# design.net
KiCad netlist of a schematic drawn in Altium Designer
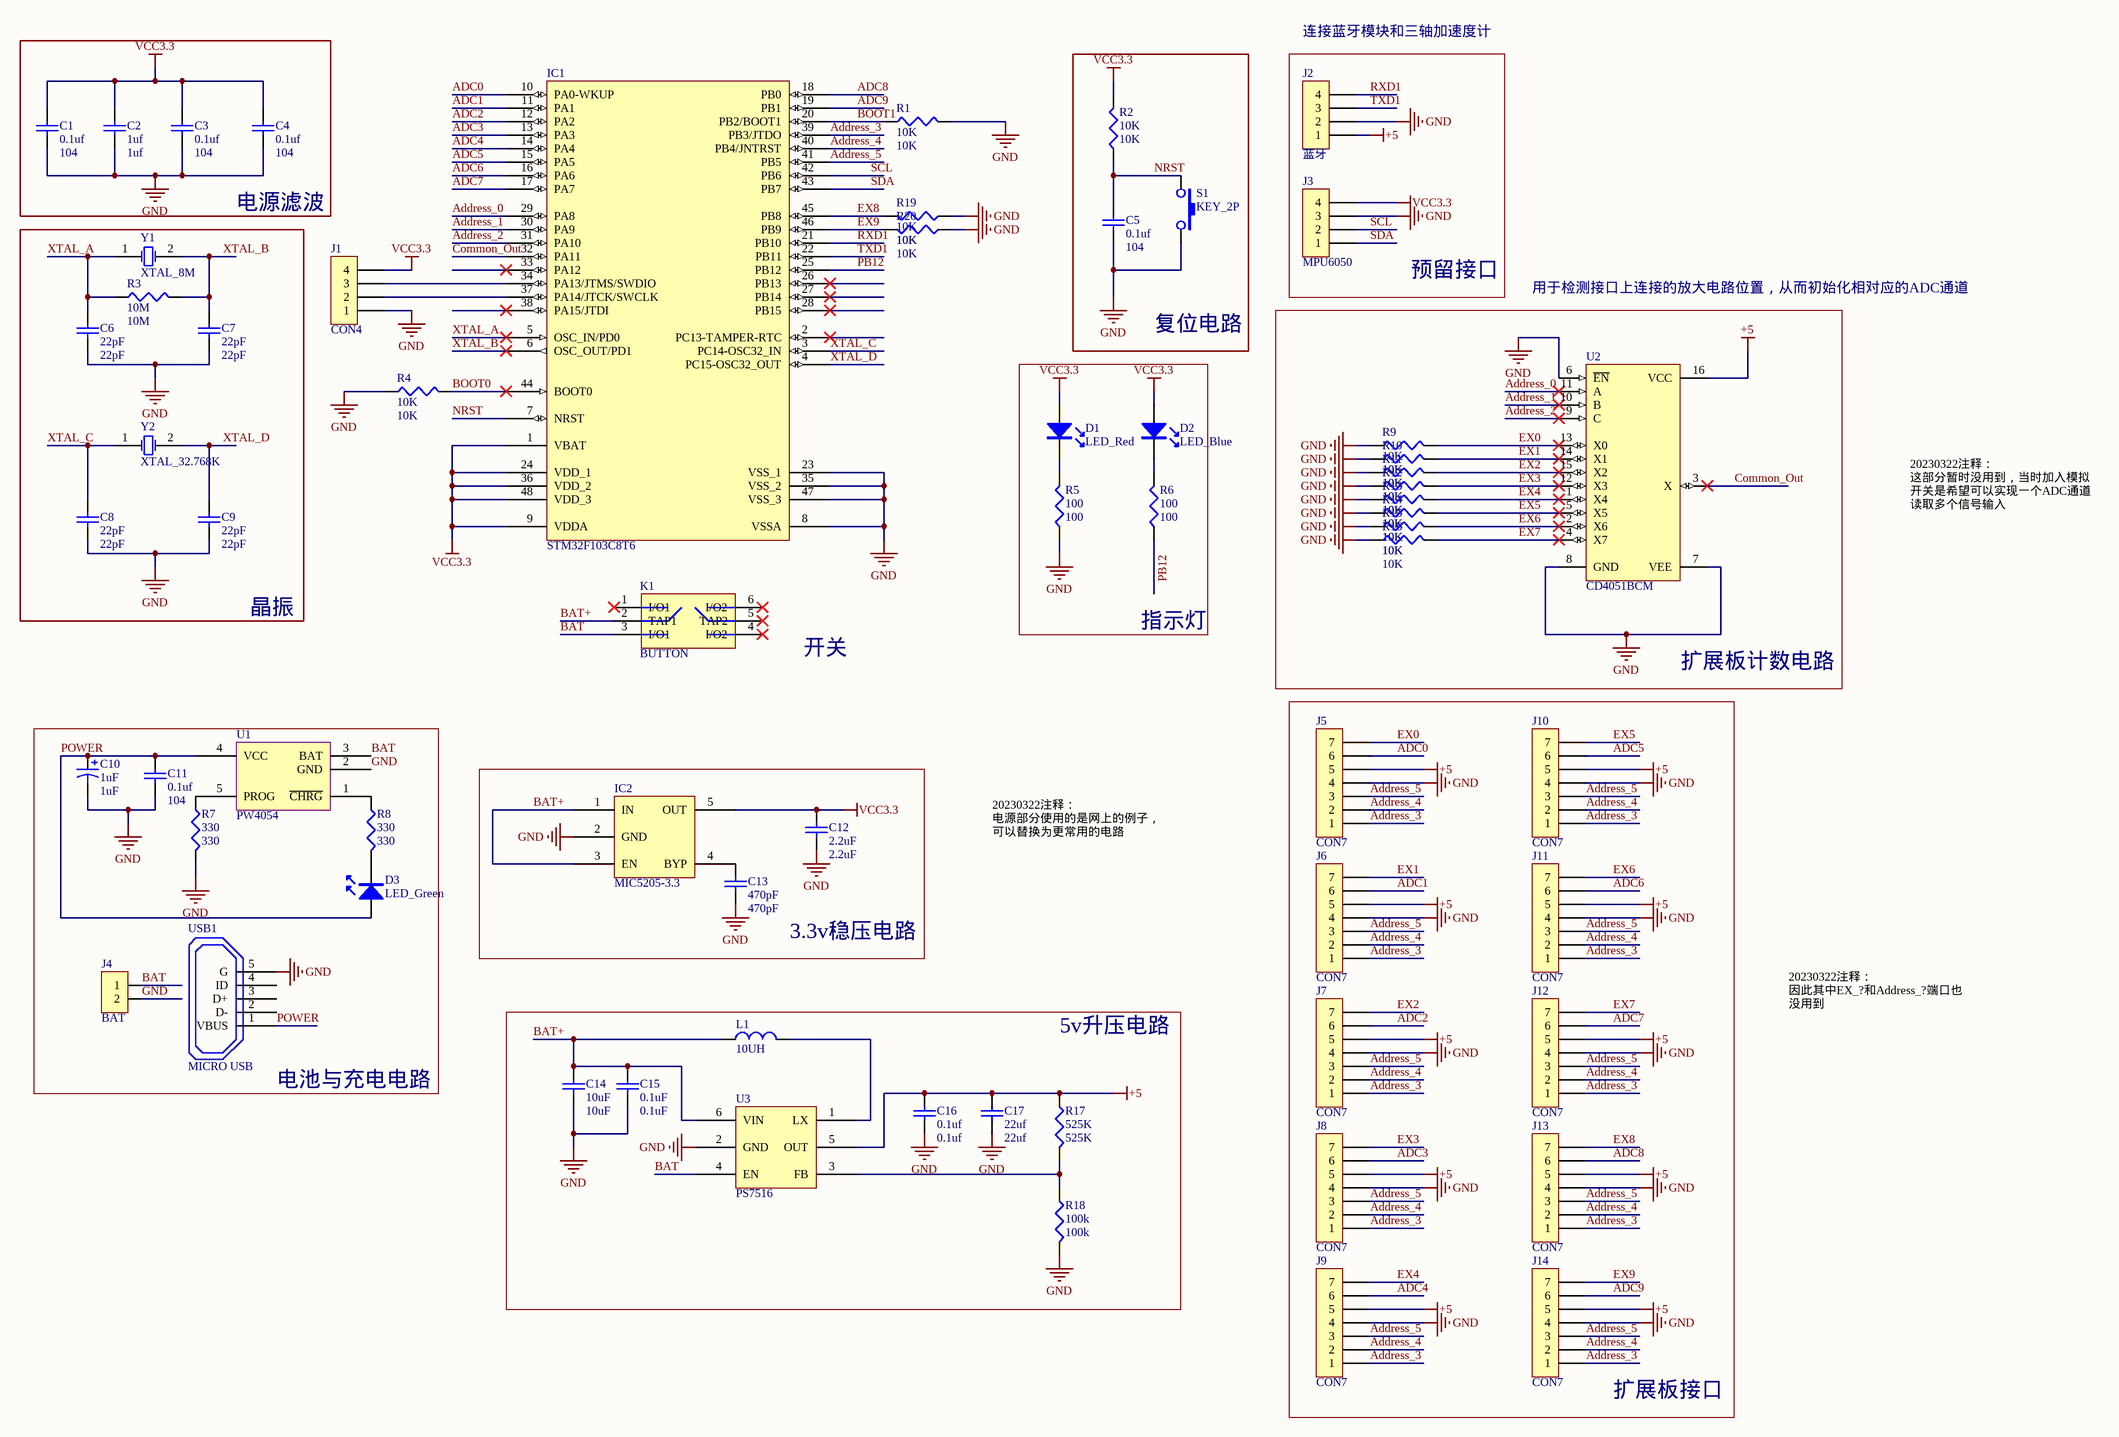
[diagram p0: 主控板原理图.SchDoc]

(export (version "E")
  (design (tool "Eeschema 10.0.6"))
  (components
    (comp (ref "C1")
      (value "0.1uf")
      (footprint "6-0805_L")
      (description "Capacitor (Semiconductor SIM Model)")
      (fields (field (name "ALTIUM_VALUE") "104") (field (name "PUBLISHER") "Altium Limited"))
      (libsource (lib "Miscellaneous Devices") (part "Cap Semi"))
    )
    (comp (ref "C2")
      (value "1uf")
      (footprint "6-0805_L")
      (description "Capacitor (Semiconductor SIM Model)")
      (fields (field (name "ALTIUM_VALUE") "1uf") (field (name "PUBLISHER") "Altium Limited"))
      (libsource (lib "Miscellaneous Devices") (part "Cap Semi"))
    )
    (comp (ref "C3")
      (value "0.1uf")
      (footprint "6-0805_L")
      (description "Capacitor (Semiconductor SIM Model)")
      (fields (field (name "ALTIUM_VALUE") "104") (field (name "PUBLISHER") "Altium Limited"))
      (libsource (lib "Miscellaneous Devices") (part "Cap Semi"))
    )
    (comp (ref "C4")
      (value "0.1uf")
      (footprint "6-0805_L")
      (description "Capacitor (Semiconductor SIM Model)")
      (fields (field (name "ALTIUM_VALUE") "104") (field (name "PUBLISHER") "Altium Limited"))
      (libsource (lib "Miscellaneous Devices") (part "Cap Semi"))
    )
    (comp (ref "C5")
      (value "0.1uf")
      (footprint "6-0805_L")
      (description "Capacitor (Semiconductor SIM Model)")
      (fields (field (name "ALTIUM_VALUE") "104") (field (name "PUBLISHER") "Altium Limited"))
      (libsource (lib "Miscellaneous Devices") (part "Cap Semi"))
    )
    (comp (ref "C6")
      (value "22pF")
      (footprint "6-0805_L")
      (description "Capacitor (Semiconductor SIM Model)")
      (fields (field (name "ALTIUM_VALUE") "22pF") (field (name "PUBLISHER") "Altium Limited"))
      (libsource (lib "Miscellaneous Devices") (part "Cap Semi"))
    )
    (comp (ref "C7")
      (value "22pF")
      (footprint "6-0805_L")
      (description "Capacitor (Semiconductor SIM Model)")
      (fields (field (name "ALTIUM_VALUE") "22pF") (field (name "PUBLISHER") "Altium Limited"))
      (libsource (lib "Miscellaneous Devices") (part "Cap Semi"))
    )
    (comp (ref "C8")
      (value "22pF")
      (footprint "6-0805_L")
      (description "Capacitor (Semiconductor SIM Model)")
      (fields (field (name "ALTIUM_VALUE") "22pF") (field (name "PUBLISHER") "Altium Limited"))
      (libsource (lib "Miscellaneous Devices") (part "Cap Semi"))
    )
    (comp (ref "C9")
      (value "22pF")
      (footprint "6-0805_L")
      (description "Capacitor (Semiconductor SIM Model)")
      (fields (field (name "ALTIUM_VALUE") "22pF") (field (name "PUBLISHER") "Altium Limited"))
      (libsource (lib "Miscellaneous Devices") (part "Cap Semi"))
    )
    (comp (ref "C10")
      (value "1uF")
      (footprint "C0805")
      (description "Polarized Capacitor (Surface Mount)")
      (fields (field (name "ALTIUM_VALUE") "1uF") (field (name "PUBLISHER") "Altium Limited"))
      (libsource (lib "Miscellaneous Devices") (part "Cap Pol3"))
    )
    (comp (ref "C11")
      (value "0.1uf")
      (footprint "6-0805_L")
      (description "Capacitor (Semiconductor SIM Model)")
      (fields (field (name "ALTIUM_VALUE") "104") (field (name "PUBLISHER") "Altium Limited"))
      (libsource (lib "Miscellaneous Devices") (part "Cap Semi"))
    )
    (comp (ref "C12")
      (value "2.2uF")
      (footprint "6-0805_L")
      (description "Capacitor (Semiconductor SIM Model)")
      (fields (field (name "ALTIUM_VALUE") "2.2uF") (field (name "PUBLISHER") "Altium Limited"))
      (libsource (lib "Miscellaneous Devices") (part "Cap Semi"))
    )
    (comp (ref "C13")
      (value "470pF")
      (footprint "6-0805_L")
      (description "Capacitor (Semiconductor SIM Model)")
      (fields (field (name "ALTIUM_VALUE") "470pF") (field (name "PUBLISHER") "Altium Limited"))
      (libsource (lib "Miscellaneous Devices") (part "Cap Semi"))
    )
    (comp (ref "C14")
      (value "10uF")
      (footprint "6-0805_L")
      (description "Capacitor (Semiconductor SIM Model)")
      (fields (field (name "ALTIUM_VALUE") "10uF") (field (name "PUBLISHER") "Altium Limited"))
      (libsource (lib "Miscellaneous Devices") (part "Cap Semi"))
    )
    (comp (ref "C15")
      (value "0.1uF")
      (footprint "6-0805_L")
      (description "Capacitor (Semiconductor SIM Model)")
      (fields (field (name "ALTIUM_VALUE") "0.1uF") (field (name "PUBLISHER") "Altium Limited"))
      (libsource (lib "Miscellaneous Devices") (part "Cap Semi"))
    )
    (comp (ref "C16")
      (value "0.1uf")
      (footprint "6-0805_L")
      (description "Capacitor (Semiconductor SIM Model)")
      (fields (field (name "ALTIUM_VALUE") "0.1uf") (field (name "PUBLISHER") "Altium Limited"))
      (libsource (lib "Miscellaneous Devices") (part "Cap Semi"))
    )
    (comp (ref "C17")
      (value "22uf")
      (footprint "6-0805_L")
      (description "Capacitor (Semiconductor SIM Model)")
      (fields (field (name "ALTIUM_VALUE") "22uf") (field (name "PUBLISHER") "Altium Limited"))
      (libsource (lib "Miscellaneous Devices") (part "Cap Semi"))
    )
    (comp (ref "D1")
      (value "LED_Red")
      (footprint "6-0805_M")
      (description "LED")
      (libsource (lib "Component") (part "LED"))
    )
    (comp (ref "D2")
      (value "LED_Blue")
      (footprint "6-0805_M")
      (description "LED")
      (libsource (lib "Component") (part "LED"))
    )
    (comp (ref "D3")
      (value "LED_Green")
      (footprint "6-0805_M")
      (description "LED")
      (libsource (lib "Component") (part "LED"))
    )
    (comp (ref "IC1")
      (value "STM32F103C8T6")
      (footprint "LQFP48")
      (description "单片机")
      (fields (field (name "PUBLISHER") "Altium Limited"))
      (libsource (lib "Chip") (part "STM32F103C8T6"))
    )
    (comp (ref "IC2")
      (value "MIC5205-3.3")
      (footprint "SOT-23-5")
      (description "稳压")
      (libsource (lib "Chip") (part "MIC5205-3.3"))
    )
    (comp (ref "J1")
      (value "CON4")
      (footprint "HDR1X4")
      (description "连接器")
      (libsource (lib "Connector") (part "CON4"))
    )
    (comp (ref "J2")
      (value "蓝牙")
      (footprint "HDR1X4")
      (description "Connector")
      (libsource (lib "杂元件库") (part "CON4"))
    )
    (comp (ref "J3")
      (value "MPU6050")
      (footprint "HDR1X4")
      (description "Connector")
      (libsource (lib "杂元件库") (part "CON4"))
    )
    (comp (ref "J4")
      (value "BAT")
      (footprint "HDR1X2")
      (description "Conjunctor")
      (libsource (lib "zj") (part "CON2"))
    )
    (comp (ref "J5")
      (value "CON7")
      (footprint "HDR1X7")
      (description "Connector")
      (libsource (lib "杂元件库") (part "CON7"))
    )
    (comp (ref "J6")
      (value "CON7")
      (footprint "HDR1X7")
      (description "Connector")
      (libsource (lib "杂元件库") (part "CON7"))
    )
    (comp (ref "J7")
      (value "CON7")
      (footprint "HDR1X7")
      (description "Connector")
      (libsource (lib "杂元件库") (part "CON7"))
    )
    (comp (ref "J8")
      (value "CON7")
      (footprint "HDR1X7")
      (description "Connector")
      (libsource (lib "杂元件库") (part "CON7"))
    )
    (comp (ref "J9")
      (value "CON7")
      (footprint "HDR1X7")
      (description "Connector")
      (libsource (lib "杂元件库") (part "CON7"))
    )
    (comp (ref "J10")
      (value "CON7")
      (footprint "HDR1X7")
      (description "Connector")
      (libsource (lib "杂元件库") (part "CON7"))
    )
    (comp (ref "J11")
      (value "CON7")
      (footprint "HDR1X7")
      (description "Connector")
      (libsource (lib "杂元件库") (part "CON7"))
    )
    (comp (ref "J12")
      (value "CON7")
      (footprint "HDR1X7")
      (description "Connector")
      (libsource (lib "杂元件库") (part "CON7"))
    )
    (comp (ref "J13")
      (value "CON7")
      (footprint "HDR1X7")
      (description "Connector")
      (libsource (lib "杂元件库") (part "CON7"))
    )
    (comp (ref "J14")
      (value "CON7")
      (footprint "HDR1X7")
      (description "Connector")
      (libsource (lib "杂元件库") (part "CON7"))
    )
    (comp (ref "K1")
      (value "BUTTON")
      (footprint "My:switch")
      (description "自锁按键")
      (libsource (lib "Component") (part "BUTTON"))
    )
    (comp (ref "L1")
      (value "10UH")
      (footprint "0850")
      (description "电感")
      (libsource (lib "Component") (part "Inductor"))
    )
    (comp (ref "R1")
      (value "10K")
      (footprint "6-0805_L")
      (description "Resistor")
      (fields (field (name "ALTIUM_VALUE") "10K") (field (name "PUBLISHER") "Altium Limited"))
      (libsource (lib "Miscellaneous Devices") (part "Res3"))
    )
    (comp (ref "R2")
      (value "10K")
      (footprint "6-0805_L")
      (description "Resistor")
      (fields (field (name "ALTIUM_VALUE") "10K") (field (name "PUBLISHER") "Altium Limited"))
      (libsource (lib "Miscellaneous Devices") (part "Res3"))
    )
    (comp (ref "R3")
      (value "10M")
      (footprint "6-0805_L")
      (description "Resistor")
      (fields (field (name "ALTIUM_VALUE") "10M") (field (name "PUBLISHER") "Altium Limited"))
      (libsource (lib "Miscellaneous Devices") (part "Res3"))
    )
    (comp (ref "R4")
      (value "10K")
      (footprint "6-0805_L")
      (description "Resistor")
      (fields (field (name "ALTIUM_VALUE") "10K") (field (name "PUBLISHER") "Altium Limited"))
      (libsource (lib "Miscellaneous Devices") (part "Res3"))
    )
    (comp (ref "R5")
      (value "100")
      (footprint "6-0805_L")
      (description "Resistor")
      (fields (field (name "ALTIUM_VALUE") "100") (field (name "PUBLISHER") "Altium Limited"))
      (libsource (lib "Miscellaneous Devices") (part "Res3"))
    )
    (comp (ref "R6")
      (value "100")
      (footprint "6-0805_L")
      (description "Resistor")
      (fields (field (name "ALTIUM_VALUE") "100") (field (name "PUBLISHER") "Altium Limited"))
      (libsource (lib "Miscellaneous Devices") (part "Res3"))
    )
    (comp (ref "R7")
      (value "330")
      (footprint "6-0805_L")
      (description "Resistor")
      (fields (field (name "ALTIUM_VALUE") "330") (field (name "PUBLISHER") "Altium Limited"))
      (libsource (lib "Miscellaneous Devices") (part "Res3"))
    )
    (comp (ref "R8")
      (value "330")
      (footprint "6-0805_L")
      (description "Resistor")
      (fields (field (name "ALTIUM_VALUE") "330") (field (name "PUBLISHER") "Altium Limited"))
      (libsource (lib "Miscellaneous Devices") (part "Res3"))
    )
    (comp (ref "R9")
      (value "10K")
      (footprint "6-0805_L")
      (description "Resistor")
      (fields (field (name "ALTIUM_VALUE") "10K") (field (name "PUBLISHER") "Altium Limited"))
      (libsource (lib "Miscellaneous Devices") (part "Res3"))
    )
    (comp (ref "R10")
      (value "10K")
      (footprint "6-0805_L")
      (description "Resistor")
      (fields (field (name "ALTIUM_VALUE") "10K") (field (name "PUBLISHER") "Altium Limited"))
      (libsource (lib "Miscellaneous Devices") (part "Res3"))
    )
    (comp (ref "R11")
      (value "10K")
      (footprint "6-0805_L")
      (description "Resistor")
      (fields (field (name "ALTIUM_VALUE") "10K") (field (name "PUBLISHER") "Altium Limited"))
      (libsource (lib "Miscellaneous Devices") (part "Res3"))
    )
    (comp (ref "R12")
      (value "10K")
      (footprint "6-0805_L")
      (description "Resistor")
      (fields (field (name "ALTIUM_VALUE") "10K") (field (name "PUBLISHER") "Altium Limited"))
      (libsource (lib "Miscellaneous Devices") (part "Res3"))
    )
    (comp (ref "R13")
      (value "10K")
      (footprint "6-0805_L")
      (description "Resistor")
      (fields (field (name "ALTIUM_VALUE") "10K") (field (name "PUBLISHER") "Altium Limited"))
      (libsource (lib "Miscellaneous Devices") (part "Res3"))
    )
    (comp (ref "R14")
      (value "10K")
      (footprint "6-0805_L")
      (description "Resistor")
      (fields (field (name "ALTIUM_VALUE") "10K") (field (name "PUBLISHER") "Altium Limited"))
      (libsource (lib "Miscellaneous Devices") (part "Res3"))
    )
    (comp (ref "R15")
      (value "10K")
      (footprint "6-0805_L")
      (description "Resistor")
      (fields (field (name "ALTIUM_VALUE") "10K") (field (name "PUBLISHER") "Altium Limited"))
      (libsource (lib "Miscellaneous Devices") (part "Res3"))
    )
    (comp (ref "R16")
      (value "10K")
      (footprint "6-0805_L")
      (description "Resistor")
      (fields (field (name "ALTIUM_VALUE") "10K") (field (name "PUBLISHER") "Altium Limited"))
      (libsource (lib "Miscellaneous Devices") (part "Res3"))
    )
    (comp (ref "R17")
      (value "525K")
      (footprint "6-0805_L")
      (description "Resistor")
      (fields (field (name "ALTIUM_VALUE") "525K") (field (name "PUBLISHER") "Altium Limited"))
      (libsource (lib "Miscellaneous Devices") (part "Res3"))
    )
    (comp (ref "R18")
      (value "100k")
      (footprint "6-0805_L")
      (description "Resistor")
      (fields (field (name "ALTIUM_VALUE") "100k") (field (name "PUBLISHER") "Altium Limited"))
      (libsource (lib "Miscellaneous Devices") (part "Res3"))
    )
    (comp (ref "R19")
      (value "10K")
      (footprint "6-0805_L")
      (description "Resistor")
      (fields (field (name "ALTIUM_VALUE") "10K") (field (name "PUBLISHER") "Altium Limited"))
      (libsource (lib "Miscellaneous Devices") (part "Res3"))
    )
    (comp (ref "R20")
      (value "10K")
      (footprint "6-0805_L")
      (description "Resistor")
      (fields (field (name "ALTIUM_VALUE") "10K") (field (name "PUBLISHER") "Altium Limited"))
      (libsource (lib "Miscellaneous Devices") (part "Res3"))
    )
    (comp (ref "S1")
      (value "KEY_2P")
      (footprint "My:button")
      (description "轻触按键2P")
      (libsource (lib "Component") (part "KEY_2P"))
    )
    (comp (ref "U1") (value "PW4054") (footprint "SOT-23-CT5_L") (libsource (lib "Schlib") (part "PW4054")))
    (comp (ref "U2")
      (value "CD4051BCM")
      (footprint "M16A_N")
      (description "8-Channel Analog Multiplexer/Demultiplexer")
      (fields (field (name "PUBLISHER") "Altium Limited"))
      (libsource (lib "altium-import") (part "root_0_CD4051BCM_"))
    )
    (comp (ref "U3")
      (value "PS7516")
      (footprint "SOT23-6_M")
      (libsource (lib "Integrated_Library1") (part "PS7516"))
    )
    (comp (ref "USB1")
      (value "MICRO USB")
      (footprint "MICRO USB")
      (libsource (lib "Connector") (part "MICRO USB"))
    )
    (comp (ref "Y1")
      (value "XTAL_8M")
      (footprint "xtal")
      (description "Crystal Oscillator")
      (fields (field (name "PUBLISHER") "Altium Limited"))
      (libsource (lib "Miscellaneous Devices") (part "XTAL"))
    )
    (comp (ref "Y2")
      (value "XTAL_32.768K")
      (footprint "R38")
      (description "Crystal Oscillator")
      (fields (field (name "PUBLISHER") "Altium Limited"))
      (libsource (lib "Miscellaneous Devices") (part "XTAL"))
    )
  )
  (nets
    (net (code "1") (name "+5") (class "Default")
      (node (ref "C16") (pin "2") (pinfunction "2_2") (pintype "passive"))
      (node (ref "C17") (pin "2") (pinfunction "2_2") (pintype "passive"))
      (node (ref "J10") (pin "5") (pinfunction "5_5") (pintype "passive"))
      (node (ref "J11") (pin "5") (pinfunction "5_5") (pintype "passive"))
      (node (ref "J12") (pin "5") (pinfunction "5_5") (pintype "passive"))
      (node (ref "J13") (pin "5") (pinfunction "5_5") (pintype "passive"))
      (node (ref "J14") (pin "5") (pinfunction "5_5") (pintype "passive"))
      (node (ref "J2") (pin "1") (pinfunction "1_1") (pintype "passive"))
      (node (ref "J5") (pin "5") (pinfunction "5_5") (pintype "passive"))
      (node (ref "J6") (pin "5") (pinfunction "5_5") (pintype "passive"))
      (node (ref "J7") (pin "5") (pinfunction "5_5") (pintype "passive"))
      (node (ref "J8") (pin "5") (pinfunction "5_5") (pintype "passive"))
      (node (ref "J9") (pin "5") (pinfunction "5_5") (pintype "passive"))
      (node (ref "R17") (pin "1") (pinfunction "1_1") (pintype "passive"))
      (node (ref "U2") (pin "16") (pinfunction "VCC_16") (pintype "power_in"))
      (node (ref "U3") (pin "5") (pinfunction "OUT_5") (pintype "passive"))
    )
    (net (code "2") (name "/ADC0") (class "Default")
      (node (ref "IC1") (pin "10") (pinfunction "PA0-WKUP_10") (pintype "bidirectional"))
      (node (ref "J5") (pin "6") (pinfunction "6_6") (pintype "passive"))
    )
    (net (code "3") (name "/ADC1") (class "Default")
      (node (ref "IC1") (pin "11") (pinfunction "PA1_11") (pintype "bidirectional"))
      (node (ref "J6") (pin "6") (pinfunction "6_6") (pintype "passive"))
    )
    (net (code "4") (name "/ADC2") (class "Default")
      (node (ref "IC1") (pin "12") (pinfunction "PA2_12") (pintype "bidirectional"))
      (node (ref "J7") (pin "6") (pinfunction "6_6") (pintype "passive"))
    )
    (net (code "5") (name "/ADC3") (class "Default")
      (node (ref "IC1") (pin "13") (pinfunction "PA3_13") (pintype "bidirectional"))
      (node (ref "J8") (pin "6") (pinfunction "6_6") (pintype "passive"))
    )
    (net (code "6") (name "/ADC4") (class "Default")
      (node (ref "IC1") (pin "14") (pinfunction "PA4_14") (pintype "bidirectional"))
      (node (ref "J9") (pin "6") (pinfunction "6_6") (pintype "passive"))
    )
    (net (code "7") (name "/ADC5") (class "Default")
      (node (ref "IC1") (pin "15") (pinfunction "PA5_15") (pintype "bidirectional"))
      (node (ref "J10") (pin "6") (pinfunction "6_6") (pintype "passive"))
    )
    (net (code "8") (name "/ADC6") (class "Default")
      (node (ref "IC1") (pin "16") (pinfunction "PA6_16") (pintype "bidirectional"))
      (node (ref "J11") (pin "6") (pinfunction "6_6") (pintype "passive"))
    )
    (net (code "9") (name "/ADC7") (class "Default")
      (node (ref "IC1") (pin "17") (pinfunction "PA7_17") (pintype "bidirectional"))
      (node (ref "J12") (pin "6") (pinfunction "6_6") (pintype "passive"))
    )
    (net (code "10") (name "/ADC8") (class "Default")
      (node (ref "IC1") (pin "18") (pinfunction "PB0_18") (pintype "bidirectional"))
      (node (ref "J13") (pin "6") (pinfunction "6_6") (pintype "passive"))
    )
    (net (code "11") (name "/ADC9") (class "Default")
      (node (ref "IC1") (pin "19") (pinfunction "PB1_19") (pintype "bidirectional"))
      (node (ref "J14") (pin "6") (pinfunction "6_6") (pintype "passive"))
    )
    (net (code "12") (name "/Address_0") (class "Default")
      (node (ref "IC1") (pin "29") (pinfunction "PA8_29") (pintype "bidirectional"))
      (node (ref "U2") (pin "11") (pinfunction "A_11") (pintype "input"))
    )
    (net (code "13") (name "/Address_1") (class "Default")
      (node (ref "IC1") (pin "30") (pinfunction "PA9_30") (pintype "bidirectional"))
      (node (ref "U2") (pin "10") (pinfunction "B_10") (pintype "input"))
    )
    (net (code "14") (name "/Address_2") (class "Default")
      (node (ref "IC1") (pin "31") (pinfunction "PA10_31") (pintype "bidirectional"))
      (node (ref "U2") (pin "9") (pinfunction "C_9") (pintype "input"))
    )
    (net (code "15") (name "/Address_3") (class "Default")
      (node (ref "IC1") (pin "39") (pinfunction "PB3/JTDO_39") (pintype "bidirectional"))
      (node (ref "J10") (pin "1") (pinfunction "1_1") (pintype "passive"))
      (node (ref "J11") (pin "1") (pinfunction "1_1") (pintype "passive"))
      (node (ref "J12") (pin "1") (pinfunction "1_1") (pintype "passive"))
      (node (ref "J13") (pin "1") (pinfunction "1_1") (pintype "passive"))
      (node (ref "J14") (pin "1") (pinfunction "1_1") (pintype "passive"))
      (node (ref "J5") (pin "1") (pinfunction "1_1") (pintype "passive"))
      (node (ref "J6") (pin "1") (pinfunction "1_1") (pintype "passive"))
      (node (ref "J7") (pin "1") (pinfunction "1_1") (pintype "passive"))
      (node (ref "J8") (pin "1") (pinfunction "1_1") (pintype "passive"))
      (node (ref "J9") (pin "1") (pinfunction "1_1") (pintype "passive"))
    )
    (net (code "16") (name "/Address_4") (class "Default")
      (node (ref "IC1") (pin "40") (pinfunction "PB4/JNTRST_40") (pintype "bidirectional"))
      (node (ref "J10") (pin "2") (pinfunction "2_2") (pintype "passive"))
      (node (ref "J11") (pin "2") (pinfunction "2_2") (pintype "passive"))
      (node (ref "J12") (pin "2") (pinfunction "2_2") (pintype "passive"))
      (node (ref "J13") (pin "2") (pinfunction "2_2") (pintype "passive"))
      (node (ref "J14") (pin "2") (pinfunction "2_2") (pintype "passive"))
      (node (ref "J5") (pin "2") (pinfunction "2_2") (pintype "passive"))
      (node (ref "J6") (pin "2") (pinfunction "2_2") (pintype "passive"))
      (node (ref "J7") (pin "2") (pinfunction "2_2") (pintype "passive"))
      (node (ref "J8") (pin "2") (pinfunction "2_2") (pintype "passive"))
      (node (ref "J9") (pin "2") (pinfunction "2_2") (pintype "passive"))
    )
    (net (code "17") (name "/Address_5") (class "Default")
      (node (ref "IC1") (pin "41") (pinfunction "PB5_41") (pintype "bidirectional"))
      (node (ref "J10") (pin "3") (pinfunction "3_3") (pintype "passive"))
      (node (ref "J11") (pin "3") (pinfunction "3_3") (pintype "passive"))
      (node (ref "J12") (pin "3") (pinfunction "3_3") (pintype "passive"))
      (node (ref "J13") (pin "3") (pinfunction "3_3") (pintype "passive"))
      (node (ref "J14") (pin "3") (pinfunction "3_3") (pintype "passive"))
      (node (ref "J5") (pin "3") (pinfunction "3_3") (pintype "passive"))
      (node (ref "J6") (pin "3") (pinfunction "3_3") (pintype "passive"))
      (node (ref "J7") (pin "3") (pinfunction "3_3") (pintype "passive"))
      (node (ref "J8") (pin "3") (pinfunction "3_3") (pintype "passive"))
      (node (ref "J9") (pin "3") (pinfunction "3_3") (pintype "passive"))
    )
    (net (code "18") (name "/BAT") (class "Default")
      (node (ref "J4") (pin "1") (pinfunction "1_1") (pintype "passive"))
      (node (ref "K1") (pin "3") (pinfunction "I/O1_3") (pintype "passive"))
      (node (ref "U1") (pin "3") (pinfunction "BAT_3") (pintype "passive"))
      (node (ref "U3") (pin "4") (pinfunction "EN_4") (pintype "passive"))
    )
    (net (code "19") (name "/BAT+") (class "Default")
      (node (ref "C14") (pin "2") (pinfunction "2_2") (pintype "passive"))
      (node (ref "C15") (pin "2") (pinfunction "2_2") (pintype "passive"))
      (node (ref "IC2") (pin "1") (pinfunction "IN_1") (pintype "passive"))
      (node (ref "IC2") (pin "3") (pinfunction "EN_3") (pintype "passive"))
      (node (ref "K1") (pin "2") (pinfunction "TAP1_2") (pintype "passive"))
      (node (ref "L1") (pin "1") (pinfunction "1_1") (pintype "passive"))
      (node (ref "U3") (pin "6") (pinfunction "VIN_6") (pintype "passive"))
    )
    (net (code "20") (name "/BOOT0") (class "Default")
      (node (ref "IC1") (pin "44") (pinfunction "BOOT0_44") (pintype "input"))
      (node (ref "R4") (pin "2") (pinfunction "2_2") (pintype "passive"))
    )
    (net (code "21") (name "/BOOT1") (class "Default")
      (node (ref "IC1") (pin "20") (pinfunction "PB2/BOOT1_20") (pintype "bidirectional"))
      (node (ref "R1") (pin "1") (pinfunction "1_1") (pintype "passive"))
    )
    (net (code "22") (name "/Common_Out") (class "Default")
      (node (ref "IC1") (pin "32") (pinfunction "PA11_32") (pintype "bidirectional"))
      (node (ref "U2") (pin "3") (pinfunction "X_3") (pintype "bidirectional"))
    )
    (net (code "23") (name "/EX0") (class "Default")
      (node (ref "J5") (pin "7") (pinfunction "7_7") (pintype "passive"))
      (node (ref "R9") (pin "2") (pinfunction "2_2") (pintype "passive"))
      (node (ref "U2") (pin "13") (pinfunction "X0_13") (pintype "bidirectional"))
    )
    (net (code "24") (name "/EX1") (class "Default")
      (node (ref "J6") (pin "7") (pinfunction "7_7") (pintype "passive"))
      (node (ref "R10") (pin "2") (pinfunction "2_2") (pintype "passive"))
      (node (ref "U2") (pin "14") (pinfunction "X1_14") (pintype "bidirectional"))
    )
    (net (code "25") (name "/EX2") (class "Default")
      (node (ref "J7") (pin "7") (pinfunction "7_7") (pintype "passive"))
      (node (ref "R11") (pin "2") (pinfunction "2_2") (pintype "passive"))
      (node (ref "U2") (pin "15") (pinfunction "X2_15") (pintype "bidirectional"))
    )
    (net (code "26") (name "/EX3") (class "Default")
      (node (ref "J8") (pin "7") (pinfunction "7_7") (pintype "passive"))
      (node (ref "R12") (pin "2") (pinfunction "2_2") (pintype "passive"))
      (node (ref "U2") (pin "12") (pinfunction "X3_12") (pintype "bidirectional"))
    )
    (net (code "27") (name "/EX4") (class "Default")
      (node (ref "J9") (pin "7") (pinfunction "7_7") (pintype "passive"))
      (node (ref "R13") (pin "2") (pinfunction "2_2") (pintype "passive"))
      (node (ref "U2") (pin "1") (pinfunction "X4_1") (pintype "bidirectional"))
    )
    (net (code "28") (name "/EX5") (class "Default")
      (node (ref "J10") (pin "7") (pinfunction "7_7") (pintype "passive"))
      (node (ref "R14") (pin "2") (pinfunction "2_2") (pintype "passive"))
      (node (ref "U2") (pin "5") (pinfunction "X5_5") (pintype "bidirectional"))
    )
    (net (code "29") (name "/EX6") (class "Default")
      (node (ref "J11") (pin "7") (pinfunction "7_7") (pintype "passive"))
      (node (ref "R15") (pin "2") (pinfunction "2_2") (pintype "passive"))
      (node (ref "U2") (pin "2") (pinfunction "X6_2") (pintype "bidirectional"))
    )
    (net (code "30") (name "/EX7") (class "Default")
      (node (ref "J12") (pin "7") (pinfunction "7_7") (pintype "passive"))
      (node (ref "R16") (pin "2") (pinfunction "2_2") (pintype "passive"))
      (node (ref "U2") (pin "4") (pinfunction "X7_4") (pintype "bidirectional"))
    )
    (net (code "31") (name "/EX8") (class "Default")
      (node (ref "IC1") (pin "45") (pinfunction "PB8_45") (pintype "bidirectional"))
      (node (ref "J13") (pin "7") (pinfunction "7_7") (pintype "passive"))
      (node (ref "R19") (pin "2") (pinfunction "2_2") (pintype "passive"))
    )
    (net (code "32") (name "/EX9") (class "Default")
      (node (ref "IC1") (pin "46") (pinfunction "PB9_46") (pintype "bidirectional"))
      (node (ref "J14") (pin "7") (pinfunction "7_7") (pintype "passive"))
      (node (ref "R20") (pin "2") (pinfunction "2_2") (pintype "passive"))
    )
    (net (code "33") (name "/NRST") (class "Default")
      (node (ref "C5") (pin "2") (pinfunction "2_2") (pintype "passive"))
      (node (ref "IC1") (pin "7") (pinfunction "NRST_7") (pintype "bidirectional"))
      (node (ref "R2") (pin "1") (pinfunction "1_1") (pintype "passive"))
      (node (ref "S1") (pin "1") (pinfunction "1_1") (pintype "passive"))
    )
    (net (code "34") (name "/PB12") (class "Default")
      (node (ref "IC1") (pin "25") (pinfunction "PB12_25") (pintype "bidirectional"))
      (node (ref "R6") (pin "1") (pinfunction "1_1") (pintype "passive"))
    )
    (net (code "35") (name "/POWER") (class "Default")
      (node (ref "C10") (pin "1") (pinfunction "1_1") (pintype "passive"))
      (node (ref "C11") (pin "2") (pinfunction "2_2") (pintype "passive"))
      (node (ref "D3") (pin "1") (pinfunction "1_1") (pintype "passive"))
      (node (ref "U1") (pin "4") (pinfunction "VCC_4") (pintype "passive"))
      (node (ref "USB1") (pin "1") (pinfunction "VBUS_1") (pintype "passive"))
    )
    (net (code "36") (name "/RXD1") (class "Default")
      (node (ref "IC1") (pin "21") (pinfunction "PB10_21") (pintype "bidirectional"))
      (node (ref "J2") (pin "4") (pinfunction "4_4") (pintype "passive"))
    )
    (net (code "37") (name "/SCL") (class "Default")
      (node (ref "IC1") (pin "42") (pinfunction "PB6_42") (pintype "bidirectional"))
      (node (ref "J3") (pin "2") (pinfunction "2_2") (pintype "passive"))
    )
    (net (code "38") (name "/SDA") (class "Default")
      (node (ref "IC1") (pin "43") (pinfunction "PB7_43") (pintype "bidirectional"))
      (node (ref "J3") (pin "1") (pinfunction "1_1") (pintype "passive"))
    )
    (net (code "39") (name "/TXD1") (class "Default")
      (node (ref "IC1") (pin "22") (pinfunction "PB11_22") (pintype "bidirectional"))
      (node (ref "J2") (pin "3") (pinfunction "3_3") (pintype "passive"))
    )
    (net (code "40") (name "/XTAL_A") (class "Default")
      (node (ref "C6") (pin "2") (pinfunction "2_2") (pintype "passive"))
      (node (ref "IC1") (pin "5") (pinfunction "OSC_IN/PD0_5") (pintype "input"))
      (node (ref "R3") (pin "1") (pinfunction "1_1") (pintype "passive"))
      (node (ref "Y1") (pin "1") (pinfunction "OSC1_1") (pintype "passive"))
    )
    (net (code "41") (name "/XTAL_B") (class "Default")
      (node (ref "C7") (pin "2") (pinfunction "2_2") (pintype "passive"))
      (node (ref "IC1") (pin "6") (pinfunction "OSC_OUT/PD1_6") (pintype "output"))
      (node (ref "R3") (pin "2") (pinfunction "2_2") (pintype "passive"))
      (node (ref "Y1") (pin "2") (pinfunction "OSC2_2") (pintype "passive"))
    )
    (net (code "42") (name "/XTAL_C") (class "Default")
      (node (ref "C8") (pin "2") (pinfunction "2_2") (pintype "passive"))
      (node (ref "IC1") (pin "3") (pinfunction "PC14-OSC32_IN_3") (pintype "bidirectional"))
      (node (ref "Y2") (pin "1") (pinfunction "OSC1_1") (pintype "passive"))
    )
    (net (code "43") (name "/XTAL_D") (class "Default")
      (node (ref "C9") (pin "2") (pinfunction "2_2") (pintype "passive"))
      (node (ref "IC1") (pin "4") (pinfunction "PC15-OSC32_OUT_4") (pintype "bidirectional"))
      (node (ref "Y2") (pin "2") (pinfunction "OSC2_2") (pintype "passive"))
    )
    (net (code "44") (name "GND") (class "Default")
      (node (ref "C1") (pin "1") (pinfunction "1_1") (pintype "passive"))
      (node (ref "C10") (pin "2") (pinfunction "2_2") (pintype "passive"))
      (node (ref "C11") (pin "1") (pinfunction "1_1") (pintype "passive"))
      (node (ref "C12") (pin "1") (pinfunction "1_1") (pintype "passive"))
      (node (ref "C13") (pin "1") (pinfunction "1_1") (pintype "passive"))
      (node (ref "C14") (pin "1") (pinfunction "1_1") (pintype "passive"))
      (node (ref "C15") (pin "1") (pinfunction "1_1") (pintype "passive"))
      (node (ref "C16") (pin "1") (pinfunction "1_1") (pintype "passive"))
      (node (ref "C17") (pin "1") (pinfunction "1_1") (pintype "passive"))
      (node (ref "C2") (pin "1") (pinfunction "1_1") (pintype "passive"))
      (node (ref "C3") (pin "1") (pinfunction "1_1") (pintype "passive"))
      (node (ref "C4") (pin "1") (pinfunction "1_1") (pintype "passive"))
      (node (ref "C5") (pin "1") (pinfunction "1_1") (pintype "passive"))
      (node (ref "C6") (pin "1") (pinfunction "1_1") (pintype "passive"))
      (node (ref "C7") (pin "1") (pinfunction "1_1") (pintype "passive"))
      (node (ref "C8") (pin "1") (pinfunction "1_1") (pintype "passive"))
      (node (ref "C9") (pin "1") (pinfunction "1_1") (pintype "passive"))
      (node (ref "IC1") (pin "23") (pinfunction "VSS_1_23") (pintype "power_in"))
      (node (ref "IC1") (pin "35") (pinfunction "VSS_2_35") (pintype "power_in"))
      (node (ref "IC1") (pin "47") (pinfunction "VSS_3_47") (pintype "power_in"))
      (node (ref "IC1") (pin "8") (pinfunction "VSSA_8") (pintype "power_in"))
      (node (ref "IC2") (pin "2") (pinfunction "GND_2") (pintype "passive"))
      (node (ref "J1") (pin "1") (pinfunction "1_1") (pintype "passive"))
      (node (ref "J10") (pin "4") (pinfunction "4_4") (pintype "passive"))
      (node (ref "J11") (pin "4") (pinfunction "4_4") (pintype "passive"))
      (node (ref "J12") (pin "4") (pinfunction "4_4") (pintype "passive"))
      (node (ref "J13") (pin "4") (pinfunction "4_4") (pintype "passive"))
      (node (ref "J14") (pin "4") (pinfunction "4_4") (pintype "passive"))
      (node (ref "J2") (pin "2") (pinfunction "2_2") (pintype "passive"))
      (node (ref "J3") (pin "3") (pinfunction "3_3") (pintype "passive"))
      (node (ref "J4") (pin "2") (pinfunction "2_2") (pintype "passive"))
      (node (ref "J5") (pin "4") (pinfunction "4_4") (pintype "passive"))
      (node (ref "J6") (pin "4") (pinfunction "4_4") (pintype "passive"))
      (node (ref "J7") (pin "4") (pinfunction "4_4") (pintype "passive"))
      (node (ref "J8") (pin "4") (pinfunction "4_4") (pintype "passive"))
      (node (ref "J9") (pin "4") (pinfunction "4_4") (pintype "passive"))
      (node (ref "R1") (pin "2") (pinfunction "2_2") (pintype "passive"))
      (node (ref "R10") (pin "1") (pinfunction "1_1") (pintype "passive"))
      (node (ref "R11") (pin "1") (pinfunction "1_1") (pintype "passive"))
      (node (ref "R12") (pin "1") (pinfunction "1_1") (pintype "passive"))
      (node (ref "R13") (pin "1") (pinfunction "1_1") (pintype "passive"))
      (node (ref "R14") (pin "1") (pinfunction "1_1") (pintype "passive"))
      (node (ref "R15") (pin "1") (pinfunction "1_1") (pintype "passive"))
      (node (ref "R16") (pin "1") (pinfunction "1_1") (pintype "passive"))
      (node (ref "R18") (pin "2") (pinfunction "2_2") (pintype "passive"))
      (node (ref "R19") (pin "1") (pinfunction "1_1") (pintype "passive"))
      (node (ref "R20") (pin "1") (pinfunction "1_1") (pintype "passive"))
      (node (ref "R4") (pin "1") (pinfunction "1_1") (pintype "passive"))
      (node (ref "R5") (pin "1") (pinfunction "1_1") (pintype "passive"))
      (node (ref "R7") (pin "2") (pinfunction "2_2") (pintype "passive"))
      (node (ref "R9") (pin "1") (pinfunction "1_1") (pintype "passive"))
      (node (ref "S1") (pin "2") (pinfunction "2_2") (pintype "passive"))
      (node (ref "U1") (pin "2") (pinfunction "GND_2") (pintype "passive"))
      (node (ref "U2") (pin "6") (pinfunction "~{EN}_6") (pintype "input"))
      (node (ref "U2") (pin "7") (pinfunction "VEE_7") (pintype "power_in"))
      (node (ref "U2") (pin "8") (pinfunction "GND_8") (pintype "power_in"))
      (node (ref "U3") (pin "2") (pinfunction "GND_2") (pintype "passive"))
      (node (ref "USB1") (pin "5") (pinfunction "G_5") (pintype "passive"))
    )
    (net (code "45") (name "Net-(D1-Pad2)") (class "Default")
      (node (ref "D1") (pin "2") (pinfunction "2_2") (pintype "passive"))
      (node (ref "R5") (pin "2") (pinfunction "2_2") (pintype "passive"))
    )
    (net (code "46") (name "Net-(D2-Pad2)") (class "Default")
      (node (ref "D2") (pin "2") (pinfunction "2_2") (pintype "passive"))
      (node (ref "R6") (pin "2") (pinfunction "2_2") (pintype "passive"))
    )
    (net (code "47") (name "Net-(D3-Pad2)") (class "Default")
      (node (ref "D3") (pin "2") (pinfunction "2_2") (pintype "passive"))
      (node (ref "R8") (pin "2") (pinfunction "2_2") (pintype "passive"))
    )
    (net (code "48") (name "Net-(IC1-PA13{slash}JTMS{slash}SWDIO)") (class "Default")
      (node (ref "IC1") (pin "34") (pinfunction "PA13/JTMS/SWDIO_34") (pintype "bidirectional"))
      (node (ref "J1") (pin "3") (pinfunction "3_3") (pintype "passive"))
    )
    (net (code "49") (name "Net-(IC1-PA14{slash}JTCK{slash}SWCLK)") (class "Default")
      (node (ref "IC1") (pin "37") (pinfunction "PA14/JTCK/SWCLK_37") (pintype "bidirectional"))
      (node (ref "J1") (pin "2") (pinfunction "2_2") (pintype "passive"))
    )
    (net (code "50") (name "Net-(IC2-BYP)") (class "Default")
      (node (ref "C13") (pin "2") (pinfunction "2_2") (pintype "passive"))
      (node (ref "IC2") (pin "4") (pinfunction "BYP_4") (pintype "passive"))
    )
    (net (code "51") (name "Net-(U1-PROG)") (class "Default")
      (node (ref "R7") (pin "1") (pinfunction "1_1") (pintype "passive"))
      (node (ref "U1") (pin "5") (pinfunction "PROG_5") (pintype "passive"))
    )
    (net (code "52") (name "Net-(U1-~{CHRG})") (class "Default")
      (node (ref "R8") (pin "1") (pinfunction "1_1") (pintype "passive"))
      (node (ref "U1") (pin "1") (pinfunction "~{CHRG}_1") (pintype "passive"))
    )
    (net (code "53") (name "Net-(U3-FB)") (class "Default")
      (node (ref "R17") (pin "2") (pinfunction "2_2") (pintype "passive"))
      (node (ref "R18") (pin "1") (pinfunction "1_1") (pintype "passive"))
      (node (ref "U3") (pin "3") (pinfunction "FB_3") (pintype "passive"))
    )
    (net (code "54") (name "Net-(U3-LX)") (class "Default")
      (node (ref "L1") (pin "2") (pinfunction "2_2") (pintype "passive"))
      (node (ref "U3") (pin "1") (pinfunction "LX_1") (pintype "passive"))
    )
    (net (code "55") (name "VCC3.3") (class "Default")
      (node (ref "C1") (pin "2") (pinfunction "2_2") (pintype "passive"))
      (node (ref "C12") (pin "2") (pinfunction "2_2") (pintype "passive"))
      (node (ref "C2") (pin "2") (pinfunction "2_2") (pintype "passive"))
      (node (ref "C3") (pin "2") (pinfunction "2_2") (pintype "passive"))
      (node (ref "C4") (pin "2") (pinfunction "2_2") (pintype "passive"))
      (node (ref "D1") (pin "1") (pinfunction "1_1") (pintype "passive"))
      (node (ref "D2") (pin "1") (pinfunction "1_1") (pintype "passive"))
      (node (ref "IC1") (pin "1") (pinfunction "VBAT_1") (pintype "power_in"))
      (node (ref "IC1") (pin "24") (pinfunction "VDD_1_24") (pintype "power_in"))
      (node (ref "IC1") (pin "36") (pinfunction "VDD_2_36") (pintype "power_in"))
      (node (ref "IC1") (pin "48") (pinfunction "VDD_3_48") (pintype "power_in"))
      (node (ref "IC1") (pin "9") (pinfunction "VDDA_9") (pintype "power_in"))
      (node (ref "IC2") (pin "5") (pinfunction "OUT_5") (pintype "passive"))
      (node (ref "J1") (pin "4") (pinfunction "4_4") (pintype "passive"))
      (node (ref "J3") (pin "4") (pinfunction "4_4") (pintype "passive"))
      (node (ref "R2") (pin "2") (pinfunction "2_2") (pintype "passive"))
    )
    (net (code "56") (name "unconnected-(IC1-PA12-Pad33)") (class "Default")
      (node (ref "IC1") (pin "33") (pinfunction "PA12_33") (pintype "bidirectional+no_connect"))
    )
    (net (code "57") (name "unconnected-(IC1-PA15{slash}JTDI-Pad38)") (class "Default")
      (node (ref "IC1") (pin "38") (pinfunction "PA15/JTDI_38") (pintype "bidirectional+no_connect"))
    )
    (net (code "58") (name "unconnected-(IC1-PB13-Pad26)") (class "Default")
      (node (ref "IC1") (pin "26") (pinfunction "PB13_26") (pintype "bidirectional+no_connect"))
    )
    (net (code "59") (name "unconnected-(IC1-PB14-Pad27)") (class "Default")
      (node (ref "IC1") (pin "27") (pinfunction "PB14_27") (pintype "bidirectional+no_connect"))
    )
    (net (code "60") (name "unconnected-(IC1-PB15-Pad28)") (class "Default")
      (node (ref "IC1") (pin "28") (pinfunction "PB15_28") (pintype "bidirectional+no_connect"))
    )
    (net (code "61") (name "unconnected-(IC1-PC13-TAMPER-RTC-Pad2)") (class "Default")
      (node (ref "IC1") (pin "2") (pinfunction "PC13-TAMPER-RTC_2") (pintype "bidirectional+no_connect"))
    )
    (net (code "62") (name "unconnected-(K1-I{slash}O1-Pad1)") (class "Default")
      (node (ref "K1") (pin "1") (pinfunction "I/O1_1") (pintype "passive+no_connect"))
    )
    (net (code "63") (name "unconnected-(K1-I{slash}O2-Pad4)") (class "Default")
      (node (ref "K1") (pin "4") (pinfunction "I/O2_4") (pintype "passive+no_connect"))
    )
    (net (code "64") (name "unconnected-(K1-I{slash}O2-Pad6)") (class "Default")
      (node (ref "K1") (pin "6") (pinfunction "I/O2_6") (pintype "passive+no_connect"))
    )
    (net (code "65") (name "unconnected-(K1-TAP2-Pad5)") (class "Default")
      (node (ref "K1") (pin "5") (pinfunction "TAP2_5") (pintype "passive+no_connect"))
    )
    (net (code "66") (name "unconnected-(USB1-D+-Pad3)") (class "Default")
      (node (ref "USB1") (pin "3") (pinfunction "D+_3") (pintype "passive"))
    )
    (net (code "67") (name "unconnected-(USB1-D--Pad2)") (class "Default")
      (node (ref "USB1") (pin "2") (pinfunction "D-_2") (pintype "passive"))
    )
    (net (code "68") (name "unconnected-(USB1-ID-Pad4)") (class "Default")
      (node (ref "USB1") (pin "4") (pinfunction "ID_4") (pintype "passive"))
    )
  )
)
